# Pressure.net
KiCad netlist of a schematic drawn in EAGLE
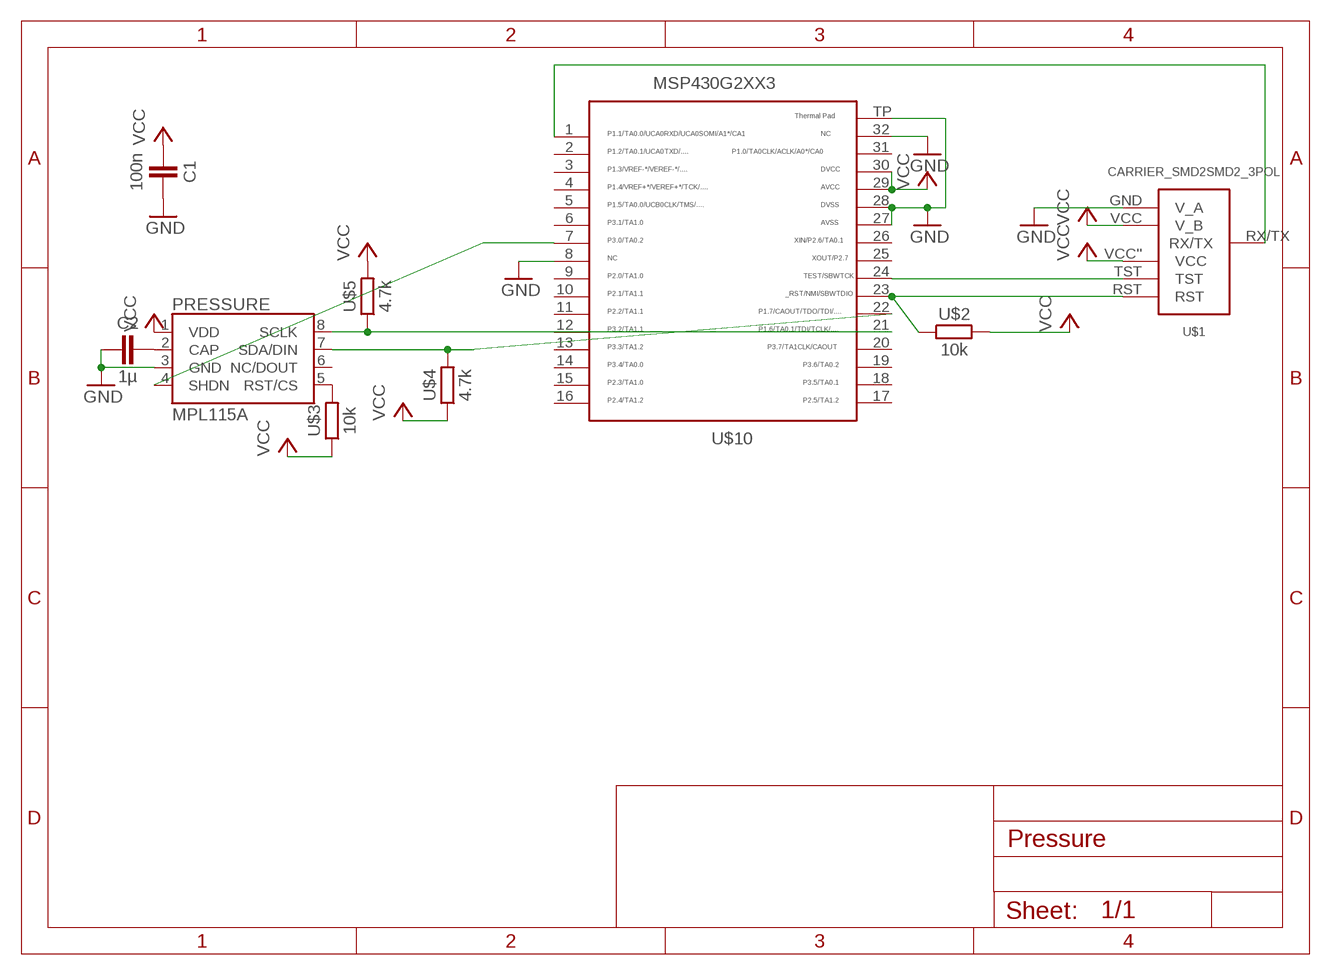
[diagram p0: schematic, sheet 1]

(export (version "E")
  (design (tool "Eeschema 10.0.6"))
  (components
    (comp (ref "C1")
      (value "100n")
      (footprint "eagle-import:603")
      (libsource (lib "eagle-import") (part "CAPACITOR"))
    )
    (comp (ref "C2")
      (value "1µ")
      (footprint "eagle-import:603")
      (libsource (lib "eagle-import") (part "CAPACITOR"))
    )
    (comp (ref "PRESSURE")
      (value "MPL115A")
      (footprint "eagle-import:LGA8")
      (libsource (lib "eagle-import") (part "MPL115A"))
    )
    (comp (ref "U$1")
      (value "CARRIER_SMD2SMD2_3POL")
      (footprint "eagle-import:CARRIER_SMD2_3POL")
      (libsource (lib "eagle-import") (part "CARRIER_SMD2SMD2_3POL"))
    )
    (comp (ref "U$2")
      (value "10k")
      (footprint "eagle-import:603")
      (libsource (lib "eagle-import") (part "RESISTOR0603"))
    )
    (comp (ref "U$3")
      (value "10k")
      (footprint "eagle-import:603")
      (libsource (lib "eagle-import") (part "RESISTOR0603"))
    )
    (comp (ref "U$4")
      (value "4.7k")
      (footprint "eagle-import:603")
      (libsource (lib "eagle-import") (part "RESISTOR0603"))
    )
    (comp (ref "U$5")
      (value "4.7k")
      (footprint "eagle-import:603")
      (libsource (lib "eagle-import") (part "RESISTOR0603"))
    )
    (comp (ref "U$10")
      (value "MSP430G2553")
      (footprint "eagle-import:QFN32")
      (libsource (lib "eagle-import") (part "MSP430G2553"))
    )
  )
  (nets
    (net (code "1") (name "GND") (class "Default")
      (node (ref "C1") (pin "2") (pinfunction "2_2") (pintype "passive"))
      (node (ref "C2") (pin "1") (pinfunction "1_1") (pintype "passive"))
      (node (ref "PRESSURE") (pin "3") (pinfunction "GND_3") (pintype "bidirectional"))
      (node (ref "U$1") (pin "GND") (pinfunction "V_A_GND") (pintype "bidirectional"))
      (node (ref "U$10") (pin "27") (pinfunction "27_27") (pintype "bidirectional"))
      (node (ref "U$10") (pin "28") (pinfunction "28_28") (pintype "bidirectional"))
      (node (ref "U$10") (pin "32") (pinfunction "32_32") (pintype "bidirectional"))
      (node (ref "U$10") (pin "8") (pinfunction "8_8") (pintype "bidirectional"))
      (node (ref "U$10") (pin "TP") (pinfunction "TP_TP") (pintype "bidirectional"))
    )
    (net (code "2") (name "Net-(PRESSURE-CAP)") (class "Default")
      (node (ref "C2") (pin "2") (pinfunction "2_2") (pintype "passive"))
      (node (ref "PRESSURE") (pin "2") (pinfunction "CAP_2") (pintype "bidirectional"))
    )
    (net (code "3") (name "Net-(PRESSURE-RST{slash}CS)") (class "Default")
      (node (ref "PRESSURE") (pin "5") (pinfunction "RST/CS_5") (pintype "bidirectional"))
      (node (ref "U$3") (pin "2") (pinfunction "2_2") (pintype "passive"))
    )
    (net (code "4") (name "Net-(PRESSURE-SCLK)") (class "Default")
      (node (ref "PRESSURE") (pin "8") (pinfunction "SCLK_8") (pintype "bidirectional"))
      (node (ref "U$10") (pin "21") (pinfunction "21_21") (pintype "bidirectional"))
      (node (ref "U$5") (pin "1") (pinfunction "1_1") (pintype "passive"))
    )
    (net (code "5") (name "Net-(PRESSURE-SDA{slash}DIN)") (class "Default")
      (node (ref "PRESSURE") (pin "7") (pinfunction "SDA/DIN_7") (pintype "bidirectional"))
      (node (ref "U$10") (pin "22") (pinfunction "22_22") (pintype "bidirectional"))
      (node (ref "U$4") (pin "2") (pinfunction "2_2") (pintype "passive"))
    )
    (net (code "6") (name "Net-(PRESSURE-SHDN)") (class "Default")
      (node (ref "PRESSURE") (pin "4") (pinfunction "SHDN_4") (pintype "bidirectional"))
      (node (ref "U$10") (pin "7") (pinfunction "7_7") (pintype "bidirectional"))
    )
    (net (code "7") (name "Net-(U$1-PadRST)") (class "Default")
      (node (ref "U$1") (pin "RST") (pinfunction "RST_RST") (pintype "bidirectional"))
      (node (ref "U$10") (pin "23") (pinfunction "23_23") (pintype "bidirectional"))
      (node (ref "U$2") (pin "1") (pinfunction "1_1") (pintype "passive"))
    )
    (net (code "8") (name "Net-(U$1-PadRX{slash}TX)") (class "Default")
      (node (ref "U$1") (pin "RX/TX") (pinfunction "RX/TX_RX/TX") (pintype "bidirectional"))
      (node (ref "U$10") (pin "1") (pinfunction "1_1") (pintype "bidirectional"))
    )
    (net (code "9") (name "Net-(U$1-PadTST)") (class "Default")
      (node (ref "U$1") (pin "TST") (pinfunction "TST_TST") (pintype "bidirectional"))
      (node (ref "U$10") (pin "24") (pinfunction "24_24") (pintype "bidirectional"))
    )
    (net (code "10") (name "VCC") (class "Default")
      (node (ref "C1") (pin "1") (pinfunction "1_1") (pintype "passive"))
      (node (ref "PRESSURE") (pin "1") (pinfunction "VDD_1") (pintype "bidirectional"))
      (node (ref "U$1") (pin "VCC") (pinfunction "V_B_VCC") (pintype "bidirectional"))
      (node (ref "U$1") (pin "VCC''") (pinfunction "VCC_VCC''") (pintype "bidirectional"))
      (node (ref "U$10") (pin "29") (pinfunction "29_29") (pintype "bidirectional"))
      (node (ref "U$10") (pin "30") (pinfunction "30_30") (pintype "bidirectional"))
      (node (ref "U$2") (pin "2") (pinfunction "2_2") (pintype "passive"))
      (node (ref "U$3") (pin "1") (pinfunction "1_1") (pintype "passive"))
      (node (ref "U$4") (pin "1") (pinfunction "1_1") (pintype "passive"))
      (node (ref "U$5") (pin "2") (pinfunction "2_2") (pintype "passive"))
    )
    (net (code "11") (name "unconnected-(PRESSURE-NC{slash}DOUT-Pad6)") (class "Default")
      (node (ref "PRESSURE") (pin "6") (pinfunction "NC/DOUT_6") (pintype "bidirectional"))
    )
    (net (code "12") (name "unconnected-(U$10-Pad2)") (class "Default")
      (node (ref "U$10") (pin "2") (pinfunction "2_2") (pintype "bidirectional"))
    )
    (net (code "13") (name "unconnected-(U$10-Pad3)") (class "Default")
      (node (ref "U$10") (pin "3") (pinfunction "3_3") (pintype "bidirectional"))
    )
    (net (code "14") (name "unconnected-(U$10-Pad4)") (class "Default")
      (node (ref "U$10") (pin "4") (pinfunction "4_4") (pintype "bidirectional"))
    )
    (net (code "15") (name "unconnected-(U$10-Pad5)") (class "Default")
      (node (ref "U$10") (pin "5") (pinfunction "5_5") (pintype "bidirectional"))
    )
    (net (code "16") (name "unconnected-(U$10-Pad6)") (class "Default")
      (node (ref "U$10") (pin "6") (pinfunction "6_6") (pintype "bidirectional"))
    )
    (net (code "17") (name "unconnected-(U$10-Pad9)") (class "Default")
      (node (ref "U$10") (pin "9") (pinfunction "9_9") (pintype "bidirectional"))
    )
    (net (code "18") (name "unconnected-(U$10-Pad10)") (class "Default")
      (node (ref "U$10") (pin "10") (pinfunction "10_10") (pintype "bidirectional"))
    )
    (net (code "19") (name "unconnected-(U$10-Pad11)") (class "Default")
      (node (ref "U$10") (pin "11") (pinfunction "11_11") (pintype "bidirectional"))
    )
    (net (code "20") (name "unconnected-(U$10-Pad12)") (class "Default")
      (node (ref "U$10") (pin "12") (pinfunction "12_12") (pintype "bidirectional"))
    )
    (net (code "21") (name "unconnected-(U$10-Pad13)") (class "Default")
      (node (ref "U$10") (pin "13") (pinfunction "13_13") (pintype "bidirectional"))
    )
    (net (code "22") (name "unconnected-(U$10-Pad14)") (class "Default")
      (node (ref "U$10") (pin "14") (pinfunction "14_14") (pintype "bidirectional"))
    )
    (net (code "23") (name "unconnected-(U$10-Pad15)") (class "Default")
      (node (ref "U$10") (pin "15") (pinfunction "15_15") (pintype "bidirectional"))
    )
    (net (code "24") (name "unconnected-(U$10-Pad16)") (class "Default")
      (node (ref "U$10") (pin "16") (pinfunction "16_16") (pintype "bidirectional"))
    )
    (net (code "25") (name "unconnected-(U$10-Pad17)") (class "Default")
      (node (ref "U$10") (pin "17") (pinfunction "17_17") (pintype "bidirectional"))
    )
    (net (code "26") (name "unconnected-(U$10-Pad18)") (class "Default")
      (node (ref "U$10") (pin "18") (pinfunction "18_18") (pintype "bidirectional"))
    )
    (net (code "27") (name "unconnected-(U$10-Pad19)") (class "Default")
      (node (ref "U$10") (pin "19") (pinfunction "19_19") (pintype "bidirectional"))
    )
    (net (code "28") (name "unconnected-(U$10-Pad20)") (class "Default")
      (node (ref "U$10") (pin "20") (pinfunction "20_20") (pintype "bidirectional"))
    )
    (net (code "29") (name "unconnected-(U$10-Pad25)") (class "Default")
      (node (ref "U$10") (pin "25") (pinfunction "25_25") (pintype "bidirectional"))
    )
    (net (code "30") (name "unconnected-(U$10-Pad26)") (class "Default")
      (node (ref "U$10") (pin "26") (pinfunction "26_26") (pintype "bidirectional"))
    )
    (net (code "31") (name "unconnected-(U$10-Pad31)") (class "Default")
      (node (ref "U$10") (pin "31") (pinfunction "31_31") (pintype "bidirectional"))
    )
  )
)
